# Receiver_SCH.net
KiCad netlist of a schematic drawn in Altium Designer
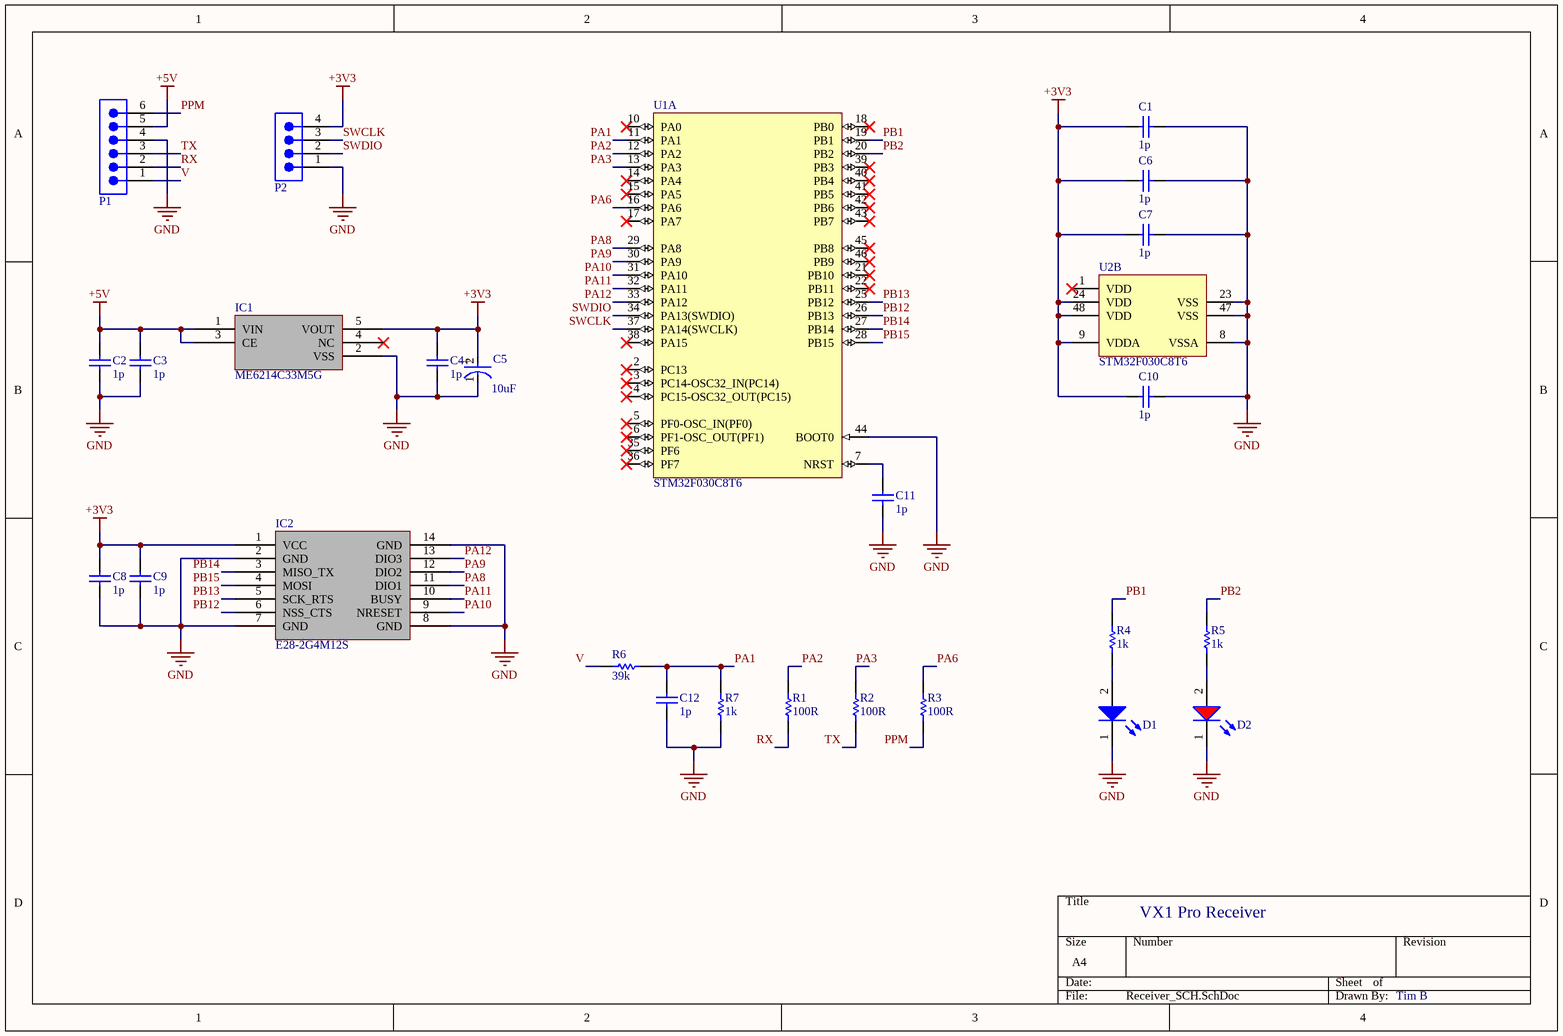
[diagram p0: Receiver_SCH.SchDoc]

(export (version "E")
  (design (tool "Eeschema 10.0.6"))
  (components
    (comp (ref "C1")
      (value "1p")
      (description "Capacitor")
      (libsource (lib "Simulation Generic Components") (part "Capacitor"))
    )
    (comp (ref "C2")
      (value "1p")
      (description "Capacitor")
      (libsource (lib "Simulation Generic Components") (part "Capacitor"))
    )
    (comp (ref "C3")
      (value "1p")
      (description "Capacitor")
      (libsource (lib "Simulation Generic Components") (part "Capacitor"))
    )
    (comp (ref "C4")
      (value "1p")
      (description "Capacitor")
      (libsource (lib "Simulation Generic Components") (part "Capacitor"))
    )
    (comp (ref "C5")
      (value "TAJB106K016RNJ")
      (footprint "FP-TAJB-MFG")
      (description "10uF 16V  ±10% 2.8Ω 1210  SMD Tantalum Capacitor")
      (fields
        (field (name "CAPACITANCE") "10uF")
        (field (name "VOLTAGE") "10V")
        (field (name "TOLERANCE") "10%")
      )
      (libsource (lib "Altium Content Vault") (part "203bc49f2ac43e59fd269a8c329ed05"))
    )
    (comp (ref "C6")
      (value "1p")
      (description "Capacitor")
      (libsource (lib "Simulation Generic Components") (part "Capacitor"))
    )
    (comp (ref "C7")
      (value "1p")
      (description "Capacitor")
      (libsource (lib "Simulation Generic Components") (part "Capacitor"))
    )
    (comp (ref "C8")
      (value "1p")
      (description "Capacitor")
      (libsource (lib "Simulation Generic Components") (part "Capacitor"))
    )
    (comp (ref "C9")
      (value "1p")
      (description "Capacitor")
      (libsource (lib "Simulation Generic Components") (part "Capacitor"))
    )
    (comp (ref "C10")
      (value "1p")
      (description "Capacitor")
      (libsource (lib "Simulation Generic Components") (part "Capacitor"))
    )
    (comp (ref "C11")
      (value "1p")
      (description "Capacitor")
      (libsource (lib "Simulation Generic Components") (part "Capacitor"))
    )
    (comp (ref "C12")
      (value "1p")
      (description "Capacitor")
      (libsource (lib "Simulation Generic Components") (part "Capacitor"))
    )
    (comp (ref "D1")
      (value "150060BS75000")
      (footprint "WL-SMCW_0603_150060xx75000")
      (libsource (lib "Altium Content Vault") (part "LED_Blue_2A-1K"))
    )
    (comp (ref "D2")
      (value "150060SS75000")
      (footprint "WL-SMCW_0603_150060xx75000")
      (libsource (lib "Altium Content Vault") (part "LED_Red_2A-1K"))
    )
    (comp (ref "IC1")
      (value "ME6214C33M5G")
      (footprint "MICRONE SOT-23-5")
      (libsource (lib "LDO") (part "MICRONE ME6214C33M5G"))
    )
    (comp (ref "IC2")
      (value "E28-2G4M12S")
      (footprint "EBYTE E28-2G4M12S")
      (libsource (lib "RF modules") (part "Ebyte E28-2G4M12S"))
    )
    (comp (ref "P1")
      (value "61300611121")
      (footprint "61300611121")
      (description "WR-PHD Pin Header, THT, Vertical, pitch 2.54mm, 1 Row, 6P")
      (fields (field (name "MANUFACTURER") "Wurth Elektronik"))
      (libsource (lib "WR-PHD") (part "61300611121"))
    )
    (comp (ref "P2")
      (value "61300411121")
      (footprint "61300411121")
      (description "WR-PHD Pin Header, THT, Vertical, pitch 2.54mm, 1 Row, 4P")
      (fields (field (name "MANUFACTURER") "Wurth Elektronik"))
      (libsource (lib "WR-PHD") (part "61300411121"))
    )
    (comp (ref "R1")
      (value "ERJ-2RKF1000X")
      (footprint "RESC1005X40X25LL05T05")
      (description "Chip Resistor, 100 Ohm, +/- 1%, 100 mW, -55 to 155 degC, 0402 (1005 Metric), RoHS, Tape and Reel")
      (fields
        (field (name "MANUFACTURER") "Basic Passives")
        (field (name "TOLERANCE") "1%")
        (field (name "RESISTANCE") "100R")
      )
      (libsource (lib "Altium Content Vault") (part "RES-2"))
    )
    (comp (ref "R2")
      (value "ERJ-2RKF1000X")
      (footprint "RESC1005X40X25LL05T05")
      (description "Chip Resistor, 100 Ohm, +/- 1%, 100 mW, -55 to 155 degC, 0402 (1005 Metric), RoHS, Tape and Reel")
      (fields
        (field (name "MANUFACTURER") "Basic Passives")
        (field (name "TOLERANCE") "1%")
        (field (name "RESISTANCE") "100R")
      )
      (libsource (lib "Altium Content Vault") (part "RES-2"))
    )
    (comp (ref "R3")
      (value "ERJ-2RKF1000X")
      (footprint "RESC1005X40X25LL05T05")
      (description "Chip Resistor, 100 Ohm, +/- 1%, 100 mW, -55 to 155 degC, 0402 (1005 Metric), RoHS, Tape and Reel")
      (fields
        (field (name "MANUFACTURER") "Basic Passives")
        (field (name "TOLERANCE") "1%")
        (field (name "RESISTANCE") "100R")
      )
      (libsource (lib "Altium Content Vault") (part "RES-2"))
    )
    (comp (ref "R4")
      (value "1k")
      (footprint "RESC1005X40X20LL05T10")
      (fields (field (name "PART NUMBER") "TNPW04021K00BETD") (field (name "MANUFACTURER") "Vishay Dale"))
      (libsource (lib "Altium Content Vault") (part "RES"))
    )
    (comp (ref "R5")
      (value "1k")
      (footprint "RESC1005X40X20LL05T10")
      (fields (field (name "PART NUMBER") "TNPW04021K00BETD") (field (name "MANUFACTURER") "Vishay Dale"))
      (libsource (lib "Altium Content Vault") (part "RES"))
    )
    (comp (ref "R6")
      (value "39k")
      (footprint "RESC2013X70X40LL20T20")
      (fields (field (name "PART NUMBER") "ERJ6ENF3902V") (field (name "MANUFACTURER") "Panasonic"))
      (libsource (lib "Altium Content Vault") (part "RES"))
    )
    (comp (ref "R7")
      (value "1k")
      (footprint "RESC1005X40X20LL05T10")
      (fields (field (name "PART NUMBER") "TNPW04021K00BETD") (field (name "MANUFACTURER") "Vishay Dale"))
      (libsource (lib "Altium Content Vault") (part "RES"))
    )
    (comp (ref "U1")
      (value "STM32F030C8T6")
      (footprint "STM-LQFP48_M")
      (libsource (lib "Altium Content Vault") (part "MC-ARM-STM32F030_X8-SQ48"))
    )
    (comp (ref "U2")
      (value "STM32F030C8T6")
      (footprint "STM-LQFP48_M")
      (libsource (lib "Altium Content Vault") (part "MC-ARM-STM32F030_X8-SQ48"))
    )
  )
  (nets
    (net (code "1") (name "+3V3") (class "Default")
      (node (ref "C1") (pin "2") (pinfunction "2_2") (pintype "passive"))
      (node (ref "C10") (pin "2") (pinfunction "2_2") (pintype "passive"))
      (node (ref "C4") (pin "2") (pinfunction "2_2") (pintype "passive"))
      (node (ref "C5") (pin "2") (pinfunction "A_2") (pintype "passive"))
      (node (ref "C6") (pin "2") (pinfunction "2_2") (pintype "passive"))
      (node (ref "C7") (pin "2") (pinfunction "2_2") (pintype "passive"))
      (node (ref "C8") (pin "2") (pinfunction "2_2") (pintype "passive"))
      (node (ref "C9") (pin "2") (pinfunction "2_2") (pintype "passive"))
      (node (ref "IC1") (pin "5") (pinfunction "VOUT_5") (pintype "passive"))
      (node (ref "IC2") (pin "1") (pinfunction "VCC_1") (pintype "power_in"))
      (node (ref "P2") (pin "4") (pinfunction "4_4") (pintype "passive"))
      (node (ref "U2") (pin "24") (pinfunction "VDD_24") (pintype "power_in"))
      (node (ref "U2") (pin "48") (pinfunction "VDD_48") (pintype "power_in"))
      (node (ref "U2") (pin "9") (pinfunction "VDDA_9") (pintype "power_in"))
    )
    (net (code "2") (name "+5V") (class "Default")
      (node (ref "C2") (pin "2") (pinfunction "2_2") (pintype "passive"))
      (node (ref "C3") (pin "2") (pinfunction "2_2") (pintype "passive"))
      (node (ref "IC1") (pin "1") (pinfunction "VIN_1") (pintype "passive"))
      (node (ref "IC1") (pin "3") (pinfunction "CE_3") (pintype "passive"))
      (node (ref "P1") (pin "5") (pinfunction "5_5") (pintype "passive"))
    )
    (net (code "3") (name "/PA1") (class "Default")
      (node (ref "C12") (pin "1") (pinfunction "1_1") (pintype "passive"))
      (node (ref "R6") (pin "2") (pinfunction "2_2") (pintype "passive"))
      (node (ref "R7") (pin "2") (pinfunction "2_2") (pintype "passive"))
      (node (ref "U1") (pin "11") (pinfunction "PA1_11") (pintype "bidirectional"))
    )
    (net (code "4") (name "/PA2") (class "Default")
      (node (ref "R1") (pin "2") (pinfunction "2_2") (pintype "passive"))
      (node (ref "U1") (pin "12") (pinfunction "PA2_12") (pintype "bidirectional"))
    )
    (net (code "5") (name "/PA3") (class "Default")
      (node (ref "R2") (pin "2") (pinfunction "2_2") (pintype "passive"))
      (node (ref "U1") (pin "13") (pinfunction "PA3_13") (pintype "bidirectional"))
    )
    (net (code "6") (name "/PA6") (class "Default")
      (node (ref "R3") (pin "2") (pinfunction "2_2") (pintype "passive"))
      (node (ref "U1") (pin "16") (pinfunction "PA6_16") (pintype "bidirectional"))
    )
    (net (code "7") (name "/PA8") (class "Default")
      (node (ref "IC2") (pin "11") (pinfunction "DIO1_11") (pintype "passive"))
      (node (ref "U1") (pin "29") (pinfunction "PA8_29") (pintype "bidirectional"))
    )
    (net (code "8") (name "/PA9") (class "Default")
      (node (ref "IC2") (pin "12") (pinfunction "DIO2_12") (pintype "passive"))
      (node (ref "U1") (pin "30") (pinfunction "PA9_30") (pintype "bidirectional"))
    )
    (net (code "9") (name "/PA10") (class "Default")
      (node (ref "IC2") (pin "9") (pinfunction "NRESET_9") (pintype "passive"))
      (node (ref "U1") (pin "31") (pinfunction "PA10_31") (pintype "bidirectional"))
    )
    (net (code "10") (name "/PA11") (class "Default")
      (node (ref "IC2") (pin "10") (pinfunction "BUSY_10") (pintype "passive"))
      (node (ref "U1") (pin "32") (pinfunction "PA11_32") (pintype "bidirectional"))
    )
    (net (code "11") (name "/PA12") (class "Default")
      (node (ref "IC2") (pin "13") (pinfunction "DIO3_13") (pintype "passive"))
      (node (ref "U1") (pin "33") (pinfunction "PA12_33") (pintype "bidirectional"))
    )
    (net (code "12") (name "/PB1") (class "Default")
      (node (ref "R4") (pin "2") (pinfunction "2_2") (pintype "passive"))
      (node (ref "U1") (pin "19") (pinfunction "PB1_19") (pintype "bidirectional"))
    )
    (net (code "13") (name "/PB2") (class "Default")
      (node (ref "R5") (pin "2") (pinfunction "2_2") (pintype "passive"))
      (node (ref "U1") (pin "20") (pinfunction "PB2_20") (pintype "bidirectional"))
    )
    (net (code "14") (name "/PB12") (class "Default")
      (node (ref "IC2") (pin "6") (pinfunction "NSS_CTS_6") (pintype "passive"))
      (node (ref "U1") (pin "26") (pinfunction "PB13_26") (pintype "bidirectional"))
    )
    (net (code "15") (name "/PB13") (class "Default")
      (node (ref "IC2") (pin "5") (pinfunction "SCK_RTS_5") (pintype "passive"))
      (node (ref "U1") (pin "25") (pinfunction "PB12_25") (pintype "bidirectional"))
    )
    (net (code "16") (name "/PB14") (class "Default")
      (node (ref "IC2") (pin "3") (pinfunction "MISO_TX_3") (pintype "passive"))
      (node (ref "U1") (pin "27") (pinfunction "PB14_27") (pintype "bidirectional"))
    )
    (net (code "17") (name "/PB15") (class "Default")
      (node (ref "IC2") (pin "4") (pinfunction "MOSI_4") (pintype "passive"))
      (node (ref "U1") (pin "28") (pinfunction "PB15_28") (pintype "bidirectional"))
    )
    (net (code "18") (name "/PPM") (class "Default")
      (node (ref "P1") (pin "6") (pinfunction "6_6") (pintype "passive"))
      (node (ref "R3") (pin "1") (pinfunction "1_1") (pintype "passive"))
    )
    (net (code "19") (name "/RX") (class "Default")
      (node (ref "P1") (pin "2") (pinfunction "2_2") (pintype "passive"))
      (node (ref "R1") (pin "1") (pinfunction "1_1") (pintype "passive"))
    )
    (net (code "20") (name "/SWCLK") (class "Default")
      (node (ref "P2") (pin "3") (pinfunction "3_3") (pintype "passive"))
      (node (ref "U1") (pin "37") (pinfunction "PA14(SWCLK)_37") (pintype "bidirectional"))
    )
    (net (code "21") (name "/SWDIO") (class "Default")
      (node (ref "P2") (pin "2") (pinfunction "2_2") (pintype "passive"))
      (node (ref "U1") (pin "34") (pinfunction "PA13(SWDIO)_34") (pintype "bidirectional"))
    )
    (net (code "22") (name "/TX") (class "Default")
      (node (ref "P1") (pin "3") (pinfunction "3_3") (pintype "passive"))
      (node (ref "R2") (pin "1") (pinfunction "1_1") (pintype "passive"))
    )
    (net (code "23") (name "/V") (class "Default")
      (node (ref "P1") (pin "1") (pinfunction "1_1") (pintype "passive"))
      (node (ref "R6") (pin "1") (pinfunction "1_1") (pintype "passive"))
    )
    (net (code "24") (name "GND") (class "Default")
      (node (ref "C1") (pin "1") (pinfunction "1_1") (pintype "passive"))
      (node (ref "C10") (pin "1") (pinfunction "1_1") (pintype "passive"))
      (node (ref "C11") (pin "1") (pinfunction "1_1") (pintype "passive"))
      (node (ref "C12") (pin "2") (pinfunction "2_2") (pintype "passive"))
      (node (ref "C2") (pin "1") (pinfunction "1_1") (pintype "passive"))
      (node (ref "C3") (pin "1") (pinfunction "1_1") (pintype "passive"))
      (node (ref "C4") (pin "1") (pinfunction "1_1") (pintype "passive"))
      (node (ref "C5") (pin "1") (pinfunction "C_1") (pintype "passive"))
      (node (ref "C6") (pin "1") (pinfunction "1_1") (pintype "passive"))
      (node (ref "C7") (pin "1") (pinfunction "1_1") (pintype "passive"))
      (node (ref "C8") (pin "1") (pinfunction "1_1") (pintype "passive"))
      (node (ref "C9") (pin "1") (pinfunction "1_1") (pintype "passive"))
      (node (ref "D1") (pin "1") (pinfunction "K_1") (pintype "passive"))
      (node (ref "D2") (pin "1") (pinfunction "K_1") (pintype "passive"))
      (node (ref "IC1") (pin "2") (pinfunction "VSS_2") (pintype "passive"))
      (node (ref "IC2") (pin "14") (pinfunction "GND_14") (pintype "power_in"))
      (node (ref "IC2") (pin "2") (pinfunction "GND_2") (pintype "passive"))
      (node (ref "IC2") (pin "7") (pinfunction "GND_7") (pintype "power_in"))
      (node (ref "IC2") (pin "8") (pinfunction "GND_8") (pintype "power_in"))
      (node (ref "P1") (pin "4") (pinfunction "4_4") (pintype "passive"))
      (node (ref "P2") (pin "1") (pinfunction "1_1") (pintype "passive"))
      (node (ref "R7") (pin "1") (pinfunction "1_1") (pintype "passive"))
      (node (ref "U1") (pin "44") (pinfunction "BOOT0_44") (pintype "input"))
      (node (ref "U2") (pin "23") (pinfunction "VSS_23") (pintype "power_in"))
      (node (ref "U2") (pin "47") (pinfunction "VSS_47") (pintype "power_in"))
      (node (ref "U2") (pin "8") (pinfunction "VSSA_8") (pintype "power_in"))
    )
    (net (code "25") (name "Net-(D1-A)") (class "Default")
      (node (ref "D1") (pin "2") (pinfunction "A_2") (pintype "passive"))
      (node (ref "R4") (pin "1") (pinfunction "1_1") (pintype "passive"))
    )
    (net (code "26") (name "Net-(D2-A)") (class "Default")
      (node (ref "D2") (pin "2") (pinfunction "A_2") (pintype "passive"))
      (node (ref "R5") (pin "1") (pinfunction "1_1") (pintype "passive"))
    )
    (net (code "27") (name "Net-(U1A-NRST)") (class "Default")
      (node (ref "C11") (pin "2") (pinfunction "2_2") (pintype "passive"))
      (node (ref "U1") (pin "7") (pinfunction "NRST_7") (pintype "bidirectional"))
    )
    (net (code "28") (name "unconnected-(IC1-NC-Pad4)") (class "Default")
      (node (ref "IC1") (pin "4") (pinfunction "NC_4") (pintype "passive+no_connect"))
    )
    (net (code "29") (name "unconnected-(U1A-PA0-Pad10)") (class "Default")
      (node (ref "U1") (pin "10") (pinfunction "PA0_10") (pintype "bidirectional+no_connect"))
    )
    (net (code "30") (name "unconnected-(U1A-PA4-Pad14)") (class "Default")
      (node (ref "U1") (pin "14") (pinfunction "PA4_14") (pintype "bidirectional+no_connect"))
    )
    (net (code "31") (name "unconnected-(U1A-PA5-Pad15)") (class "Default")
      (node (ref "U1") (pin "15") (pinfunction "PA5_15") (pintype "bidirectional+no_connect"))
    )
    (net (code "32") (name "unconnected-(U1A-PA7-Pad17)") (class "Default")
      (node (ref "U1") (pin "17") (pinfunction "PA7_17") (pintype "bidirectional+no_connect"))
    )
    (net (code "33") (name "unconnected-(U1A-PA15-Pad38)") (class "Default")
      (node (ref "U1") (pin "38") (pinfunction "PA15_38") (pintype "bidirectional+no_connect"))
    )
    (net (code "34") (name "unconnected-(U1A-PB0-Pad18)") (class "Default")
      (node (ref "U1") (pin "18") (pinfunction "PB0_18") (pintype "bidirectional+no_connect"))
    )
    (net (code "35") (name "unconnected-(U1A-PB3-Pad39)") (class "Default")
      (node (ref "U1") (pin "39") (pinfunction "PB3_39") (pintype "bidirectional+no_connect"))
    )
    (net (code "36") (name "unconnected-(U1A-PB4-Pad40)") (class "Default")
      (node (ref "U1") (pin "40") (pinfunction "PB4_40") (pintype "bidirectional+no_connect"))
    )
    (net (code "37") (name "unconnected-(U1A-PB5-Pad41)") (class "Default")
      (node (ref "U1") (pin "41") (pinfunction "PB5_41") (pintype "bidirectional+no_connect"))
    )
    (net (code "38") (name "unconnected-(U1A-PB6-Pad42)") (class "Default")
      (node (ref "U1") (pin "42") (pinfunction "PB6_42") (pintype "bidirectional+no_connect"))
    )
    (net (code "39") (name "unconnected-(U1A-PB7-Pad43)") (class "Default")
      (node (ref "U1") (pin "43") (pinfunction "PB7_43") (pintype "bidirectional+no_connect"))
    )
    (net (code "40") (name "unconnected-(U1A-PB8-Pad45)") (class "Default")
      (node (ref "U1") (pin "45") (pinfunction "PB8_45") (pintype "bidirectional+no_connect"))
    )
    (net (code "41") (name "unconnected-(U1A-PB9-Pad46)") (class "Default")
      (node (ref "U1") (pin "46") (pinfunction "PB9_46") (pintype "bidirectional+no_connect"))
    )
    (net (code "42") (name "unconnected-(U1A-PB10-Pad21)") (class "Default")
      (node (ref "U1") (pin "21") (pinfunction "PB10_21") (pintype "bidirectional+no_connect"))
    )
    (net (code "43") (name "unconnected-(U1A-PB11-Pad22)") (class "Default")
      (node (ref "U1") (pin "22") (pinfunction "PB11_22") (pintype "bidirectional+no_connect"))
    )
    (net (code "44") (name "unconnected-(U1A-PC13-Pad2)") (class "Default")
      (node (ref "U1") (pin "2") (pinfunction "PC13_2") (pintype "bidirectional+no_connect"))
    )
    (net (code "45") (name "unconnected-(U1A-PC14-OSC32_IN(PC14)-Pad3)") (class "Default")
      (node (ref "U1") (pin "3") (pinfunction "PC14-OSC32_IN(PC14)_3") (pintype "bidirectional+no_connect"))
    )
    (net (code "46") (name "unconnected-(U1A-PC15-OSC32_OUT(PC15)-Pad4)") (class "Default")
      (node (ref "U1") (pin "4") (pinfunction "PC15-OSC32_OUT(PC15)_4") (pintype "bidirectional+no_connect"))
    )
    (net (code "47") (name "unconnected-(U1A-PF0-OSC_IN(PF0)-Pad5)") (class "Default")
      (node (ref "U1") (pin "5") (pinfunction "PF0-OSC_IN(PF0)_5") (pintype "bidirectional+no_connect"))
    )
    (net (code "48") (name "unconnected-(U1A-PF1-OSC_OUT(PF1)-Pad6)") (class "Default")
      (node (ref "U1") (pin "6") (pinfunction "PF1-OSC_OUT(PF1)_6") (pintype "bidirectional+no_connect"))
    )
    (net (code "49") (name "unconnected-(U1A-PF6-Pad35)") (class "Default")
      (node (ref "U1") (pin "35") (pinfunction "PF6_35") (pintype "bidirectional+no_connect"))
    )
    (net (code "50") (name "unconnected-(U1A-PF7-Pad36)") (class "Default")
      (node (ref "U1") (pin "36") (pinfunction "PF7_36") (pintype "bidirectional+no_connect"))
    )
    (net (code "51") (name "unconnected-(U2B-VDD-Pad1)") (class "Default")
      (node (ref "U2") (pin "1") (pinfunction "VDD_1") (pintype "power_in+no_connect"))
    )
  )
)
